# main.net
KiCad netlist of a schematic drawn in EAGLE
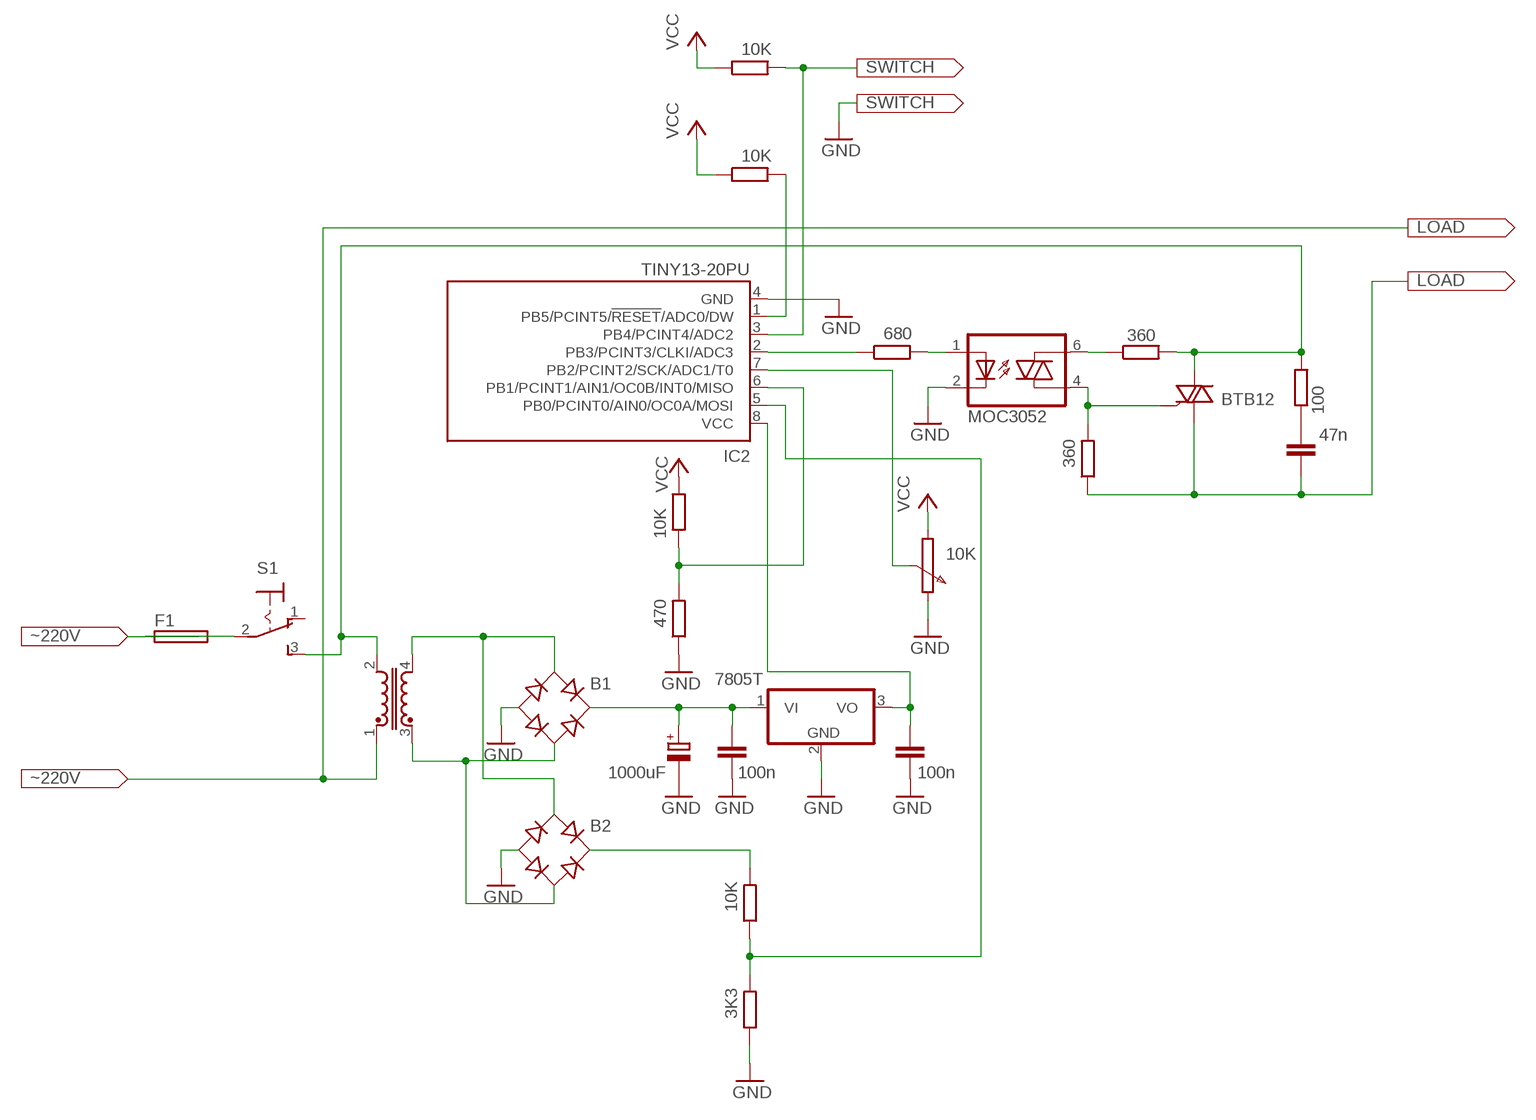
[diagram p0: schematic, sheet 1]

(export (version "E")
  (design (tool "Eeschema 10.0.6"))
  (components
    (comp (ref "B1")
      (value "MB6S")
      (footprint "eagle-import:SOIC-4")
      (libsource (lib "eagle-import") (part "MBS6"))
    )
    (comp (ref "B2")
      (value "MB6S")
      (footprint "eagle-import:SOIC-4")
      (libsource (lib "eagle-import") (part "MBS6"))
    )
    (comp (ref "F1")
      (value "FUSEGSH15")
      (footprint "eagle-import:GSH15")
      (libsource (lib "eagle-import") (part "FUSEGSH15"))
    )
    (comp (ref "IC1")
      (value "7805T")
      (footprint "eagle-import:TO220H")
      (libsource (lib "eagle-import") (part "78T05"))
    )
    (comp (ref "IC2")
      (value "TINY13-20PU")
      (footprint "eagle-import:DIL08")
      (fields (field (name "MPN") "ATTINY13-20PU"))
      (libsource (lib "eagle-import") (part "TINY13PU-20"))
    )
    (comp (ref "OK1")
      (value "MOC3052")
      (footprint "eagle-import:DIL06")
      (libsource (lib "eagle-import") (part "MOC30M22"))
    )
    (comp (ref "R1")
      (value "680")
      (footprint "eagle-import:0204_7")
      (libsource (lib "eagle-import") (part "R-EU_0204/7"))
    )
    (comp (ref "R2")
      (value "360")
      (footprint "eagle-import:0204_7")
      (libsource (lib "eagle-import") (part "R-EU_0204/7"))
    )
    (comp (ref "R3")
      (value "360")
      (footprint "eagle-import:0204_7")
      (libsource (lib "eagle-import") (part "R-EU_0204/7"))
    )
    (comp (ref "R4")
      (value "100")
      (footprint "eagle-import:0204_7")
      (libsource (lib "eagle-import") (part "R-EU_0204/7"))
    )
    (comp (ref "R5")
      (value "10K")
      (footprint "eagle-import:0204_7")
      (libsource (lib "eagle-import") (part "R-EU_0204/7"))
    )
    (comp (ref "R6")
      (value "10K")
      (footprint "eagle-import:0204_7")
      (libsource (lib "eagle-import") (part "R-EU_0204/7"))
    )
    (comp (ref "R7")
      (value "10K")
      (footprint "eagle-import:0204_7")
      (libsource (lib "eagle-import") (part "R-EU_0204/7"))
    )
    (comp (ref "R8")
      (value "3K3")
      (footprint "eagle-import:0204_7")
      (libsource (lib "eagle-import") (part "R-EU_0204/7"))
    )
    (comp (ref "R9")
      (value "10K")
      (footprint "eagle-import:0204_7")
      (libsource (lib "eagle-import") (part "R-EU_0204/7"))
    )
    (comp (ref "R10")
      (value "470")
      (footprint "eagle-import:0204_7")
      (libsource (lib "eagle-import") (part "R-EU_0204/7"))
    )
    (comp (ref "S1")
      (value "320-916")
      (footprint "eagle-import:320-916")
      (libsource (lib "eagle-import") (part "320-916"))
    )
    (comp (ref "T2")
      (value "BTB12")
      (footprint "eagle-import:TO220BV")
      (libsource (lib "eagle-import") (part "TIC206D"))
    )
    (comp (ref "TR3")
      (value "U15-TRANSFORMER")
      (footprint "eagle-import:U15")
      (libsource (lib "eagle-import") (part "U15-TRANSFORMER"))
    )
  )
  (nets
    (net (code "1") (name "GND") (class "Default")
      (node (ref "B1") (pin "-") (pinfunction "-_-") (pintype "passive"))
      (node (ref "B2") (pin "-") (pinfunction "-_-") (pintype "passive"))
      (node (ref "IC1") (pin "2") (pinfunction "GND_2") (pintype "passive"))
      (node (ref "IC2") (pin "4") (pinfunction "GND_4") (pintype "power_in"))
      (node (ref "OK1") (pin "2") (pinfunction "C_2") (pintype "passive"))
      (node (ref "R10") (pin "1") (pinfunction "1_1") (pintype "passive"))
      (node (ref "R8") (pin "1") (pinfunction "1_1") (pintype "passive"))
    )
    (net (code "2") (name "Net-(B1-AC1)") (class "Default")
      (node (ref "B1") (pin "~1") (pinfunction "AC1_~1") (pintype "passive"))
      (node (ref "B2") (pin "~1") (pinfunction "AC1_~1") (pintype "passive"))
      (node (ref "TR3") (pin "4") (pinfunction "4_4") (pintype "passive"))
    )
    (net (code "3") (name "Net-(B1-AC2)") (class "Default")
      (node (ref "B1") (pin "~2") (pinfunction "AC2_~2") (pintype "passive"))
      (node (ref "B2") (pin "~2") (pinfunction "AC2_~2") (pintype "passive"))
      (node (ref "TR3") (pin "3") (pinfunction "3_3") (pintype "passive"))
    )
    (net (code "4") (name "Net-(B2-Pad+)") (class "Default")
      (node (ref "B2") (pin "+") (pinfunction "+_+") (pintype "passive"))
      (node (ref "R7") (pin "2") (pinfunction "2_2") (pintype "passive"))
    )
    (net (code "5") (name "Net-(IC1-VI)") (class "Default")
      (node (ref "B1") (pin "+") (pinfunction "+_+") (pintype "passive"))
      (node (ref "IC1") (pin "1") (pinfunction "VI_1") (pintype "input"))
    )
    (net (code "6") (name "Net-(IC1-VO)") (class "Default")
      (node (ref "IC1") (pin "3") (pinfunction "VO_3") (pintype "passive"))
      (node (ref "IC2") (pin "8") (pinfunction "VCC_8") (pintype "power_in"))
    )
    (net (code "7") (name "Net-(IC2-PB0{slash}PCINT0{slash}AIN0{slash}OC0A{slash}MOSI)") (class "Default")
      (node (ref "IC2") (pin "5") (pinfunction "PB0/PCINT0/AIN0/OC0A/MOSI_5") (pintype "bidirectional"))
      (node (ref "R7") (pin "1") (pinfunction "1_1") (pintype "passive"))
      (node (ref "R8") (pin "2") (pinfunction "2_2") (pintype "passive"))
    )
    (net (code "8") (name "Net-(IC2-PB1{slash}PCINT1{slash}AIN1{slash}OC0B{slash}INT0{slash}MISO)") (class "Default")
      (node (ref "IC2") (pin "6") (pinfunction "PB1/PCINT1/AIN1/OC0B/INT0/MISO_6") (pintype "bidirectional"))
      (node (ref "R10") (pin "2") (pinfunction "2_2") (pintype "passive"))
      (node (ref "R9") (pin "1") (pinfunction "1_1") (pintype "passive"))
    )
    (net (code "9") (name "Net-(IC2-PB3{slash}PCINT3{slash}CLKI{slash}ADC3)") (class "Default")
      (node (ref "IC2") (pin "2") (pinfunction "PB3/PCINT3/CLKI/ADC3_2") (pintype "bidirectional"))
      (node (ref "R1") (pin "1") (pinfunction "1_1") (pintype "passive"))
    )
    (net (code "10") (name "Net-(IC2-PB4{slash}PCINT4{slash}ADC2)") (class "Default")
      (node (ref "IC2") (pin "3") (pinfunction "PB4/PCINT4/ADC2_3") (pintype "bidirectional"))
      (node (ref "R5") (pin "2") (pinfunction "2_2") (pintype "passive"))
    )
    (net (code "11") (name "Net-(IC2-PB5{slash}PCINT5{slash}~{RESET}{slash}ADC0{slash}DW)") (class "Default")
      (node (ref "IC2") (pin "1") (pinfunction "PB5/PCINT5/~{RESET}/ADC0/DW_1") (pintype "bidirectional"))
      (node (ref "R6") (pin "2") (pinfunction "2_2") (pintype "passive"))
    )
    (net (code "12") (name "Net-(OK1-A)") (class "Default")
      (node (ref "OK1") (pin "1") (pinfunction "A_1") (pintype "passive"))
      (node (ref "R1") (pin "2") (pinfunction "2_2") (pintype "passive"))
    )
    (net (code "13") (name "Net-(OK1-A1)") (class "Default")
      (node (ref "OK1") (pin "4") (pinfunction "A1_4") (pintype "passive"))
      (node (ref "R3") (pin "2") (pinfunction "2_2") (pintype "passive"))
      (node (ref "T2") (pin "G") (pinfunction "G_G") (pintype "passive"))
    )
    (net (code "14") (name "Net-(OK1-A2)") (class "Default")
      (node (ref "OK1") (pin "6") (pinfunction "A2_6") (pintype "passive"))
      (node (ref "R2") (pin "1") (pinfunction "1_1") (pintype "passive"))
    )
    (net (code "15") (name "Net-(S1-P)") (class "Default")
      (node (ref "F1") (pin "1") (pinfunction "1_1") (pintype "passive"))
      (node (ref "S1") (pin "2") (pinfunction "P_2") (pintype "passive"))
    )
    (net (code "16") (name "Net-(S1-S)") (class "Default")
      (node (ref "R2") (pin "2") (pinfunction "2_2") (pintype "passive"))
      (node (ref "R4") (pin "2") (pinfunction "2_2") (pintype "passive"))
      (node (ref "S1") (pin "3") (pinfunction "S_3") (pintype "passive"))
      (node (ref "T2") (pin "T2") (pinfunction "A2_T2") (pintype "passive"))
      (node (ref "TR3") (pin "2") (pinfunction "2_2") (pintype "passive"))
    )
    (net (code "17") (name "Net-(T2-A1)") (class "Default")
      (node (ref "R3") (pin "1") (pinfunction "1_1") (pintype "passive"))
      (node (ref "T2") (pin "T1") (pinfunction "A1_T1") (pintype "passive"))
    )
    (net (code "18") (name "VCC") (class "Default")
      (node (ref "R5") (pin "1") (pinfunction "1_1") (pintype "passive"))
      (node (ref "R6") (pin "1") (pinfunction "1_1") (pintype "passive"))
      (node (ref "R9") (pin "2") (pinfunction "2_2") (pintype "passive"))
    )
    (net (code "19") (name "unconnected-(F1-Pad2)") (class "Default")
      (node (ref "F1") (pin "2") (pinfunction "2_2") (pintype "passive"))
    )
    (net (code "20") (name "unconnected-(IC2-PB2{slash}PCINT2{slash}SCK{slash}ADC1{slash}T0-Pad7)") (class "Default")
      (node (ref "IC2") (pin "7") (pinfunction "PB2/PCINT2/SCK/ADC1/T0_7") (pintype "bidirectional"))
    )
    (net (code "21") (name "unconnected-(R4-Pad1)") (class "Default")
      (node (ref "R4") (pin "1") (pinfunction "1_1") (pintype "passive"))
    )
    (net (code "22") (name "unconnected-(S1-O-Pad1)") (class "Default")
      (node (ref "S1") (pin "1") (pinfunction "O_1") (pintype "passive"))
    )
    (net (code "23") (name "unconnected-(TR3-Pad1)") (class "Default")
      (node (ref "TR3") (pin "1") (pinfunction "1_1") (pintype "passive"))
    )
  )
)
